# KeyBoard.net
KiCad netlist of a schematic drawn in Altium Designer
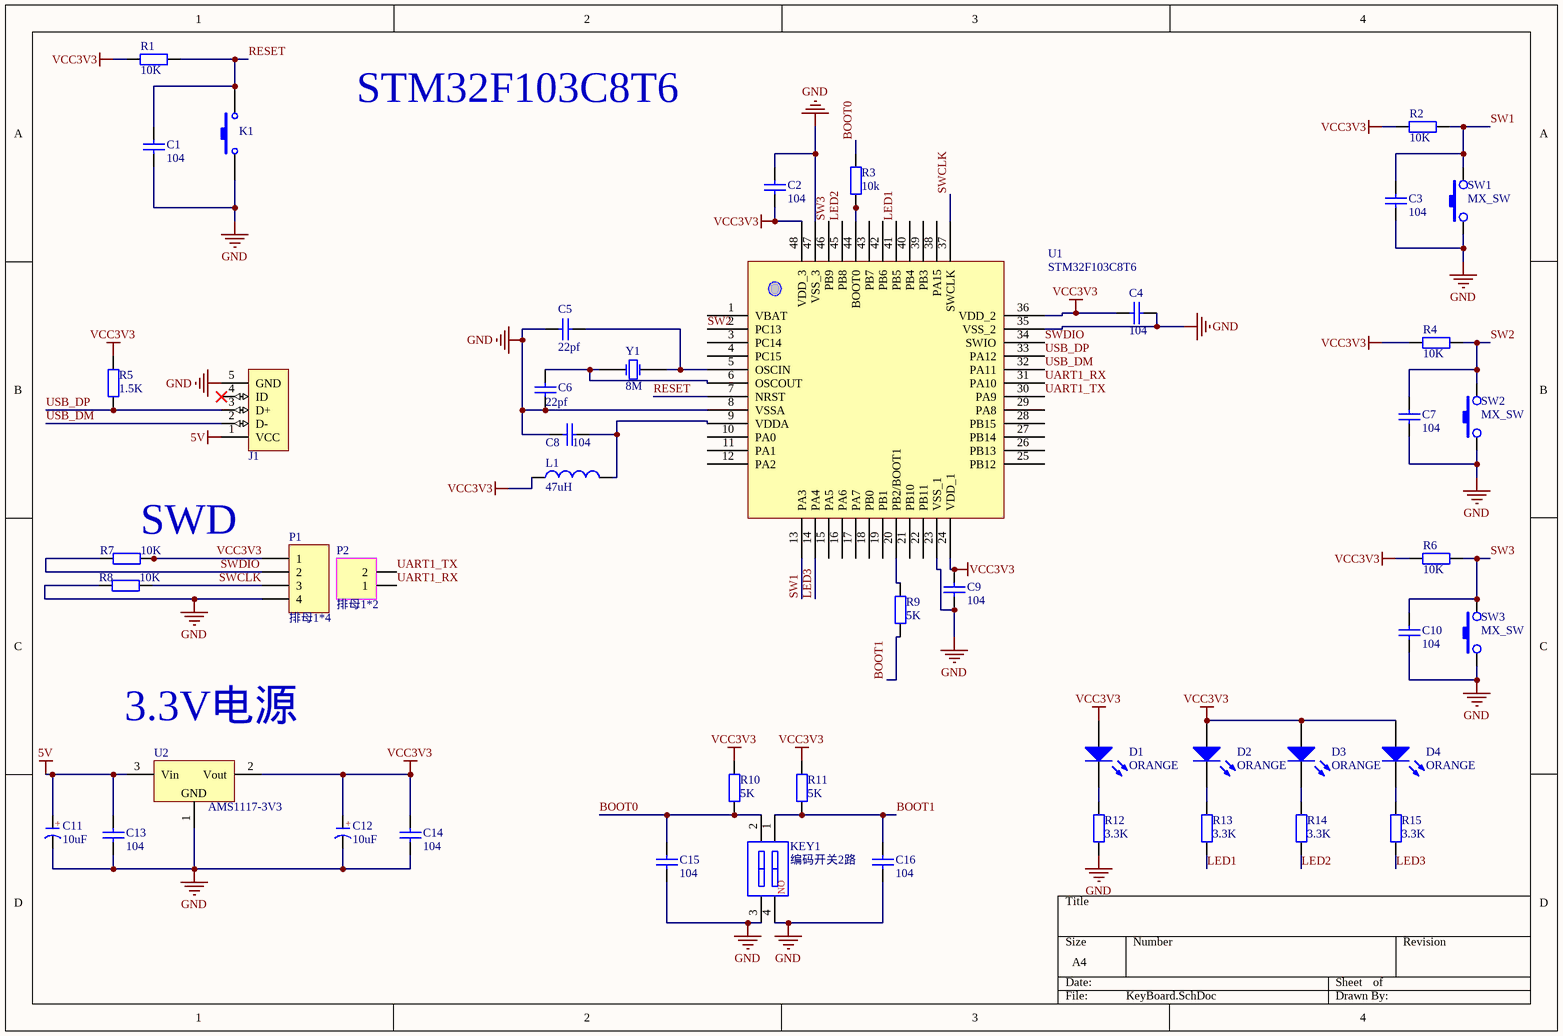
[diagram p0: KeyBoard.SchDoc]

(export (version "E")
  (design (tool "Eeschema 10.0.6"))
  (components
    (comp (ref "C1")
      (value "104")
      (footprint "C 0805")
      (description "无极性电容")
      (libsource (lib "HRT_D Schlib") (part "Cap"))
    )
    (comp (ref "C2")
      (value "104")
      (footprint "C 0805")
      (description "无极性电容")
      (libsource (lib "HRT_D Schlib") (part "Cap"))
    )
    (comp (ref "C3")
      (value "104")
      (footprint "C 0805")
      (description "无极性电容")
      (libsource (lib "HRT_D Schlib") (part "Cap"))
    )
    (comp (ref "C4")
      (value "104")
      (footprint "C 0805")
      (description "无极性电容")
      (libsource (lib "HRT_D Schlib") (part "Cap"))
    )
    (comp (ref "C5")
      (value "22pf")
      (footprint "C 0805")
      (description "无极性电容")
      (libsource (lib "HRT_D Schlib") (part "Cap"))
    )
    (comp (ref "C6")
      (value "22pf")
      (footprint "C 0805")
      (description "无极性电容")
      (libsource (lib "HRT_D Schlib") (part "Cap"))
    )
    (comp (ref "C7")
      (value "104")
      (footprint "C 0805")
      (description "无极性电容")
      (libsource (lib "HRT_D Schlib") (part "Cap"))
    )
    (comp (ref "C8")
      (value "104")
      (footprint "C 0805")
      (description "无极性电容")
      (libsource (lib "HRT_D Schlib") (part "Cap"))
    )
    (comp (ref "C9")
      (value "104")
      (footprint "C 0805")
      (description "无极性电容")
      (libsource (lib "HRT_D Schlib") (part "Cap"))
    )
    (comp (ref "C10")
      (value "104")
      (footprint "C 0805")
      (description "无极性电容")
      (libsource (lib "HRT_D Schlib") (part "Cap"))
    )
    (comp (ref "C11") (value "10uF") (footprint "CD B(3528)") (libsource (lib "电阻电容电感") (part "贴片钽电容")))
    (comp (ref "C12") (value "10uF") (footprint "CD B(3528)") (libsource (lib "电阻电容电感") (part "贴片钽电容")))
    (comp (ref "C13")
      (value "104")
      (footprint "C 0805")
      (description "无极性电容")
      (libsource (lib "HRT_D Schlib") (part "Cap"))
    )
    (comp (ref "C14")
      (value "104")
      (footprint "C 0805")
      (description "无极性电容")
      (libsource (lib "HRT_D Schlib") (part "Cap"))
    )
    (comp (ref "C15")
      (value "104")
      (footprint "C 0805")
      (description "无极性电容")
      (libsource (lib "HRT_D Schlib") (part "Cap"))
    )
    (comp (ref "C16")
      (value "104")
      (footprint "C 0805")
      (description "无极性电容")
      (libsource (lib "HRT_D Schlib") (part "Cap"))
    )
    (comp (ref "D1")
      (value "ORANGE")
      (footprint "LED_0805")
      (description "发光二极管")
      (libsource (lib "ESC_control") (part "LED"))
    )
    (comp (ref "D2")
      (value "ORANGE")
      (footprint "LED_0805")
      (description "发光二极管")
      (libsource (lib "ESC_control") (part "LED"))
    )
    (comp (ref "D3")
      (value "ORANGE")
      (footprint "LED_0805")
      (description "发光二极管")
      (libsource (lib "ESC_control") (part "LED"))
    )
    (comp (ref "D4")
      (value "ORANGE")
      (footprint "LED_0805")
      (description "发光二极管")
      (libsource (lib "ESC_control") (part "LED"))
    )
    (comp (ref "J1")
      (value "Micro USB 2.0 PORT")
      (footprint "USB_MICRO")
      (description "Micro USB 2.0 插座")
      (libsource (lib "HRT_D Schlib") (part "Micro USB 2.0 PORT"))
    )
    (comp (ref "K1")
      (value "Key")
      (footprint "KEY 3.6*2.5 SMD")
      (description "按键")
      (libsource (lib "HRT_D Schlib") (part "Key"))
    )
    (comp (ref "KEY1")
      (value "编码开关2路")
      (footprint "CSW1.27 SMD-2P")
      (libsource (lib "开关、按钮") (part "编码开关2路"))
    )
    (comp (ref "L1")
      (value "47uH")
      (footprint "L 0805")
      (description "电感")
      (libsource (lib "HRT_D Schlib") (part "Inductor"))
    )
    (comp (ref "P1") (value "排母1*4") (footprint "HDR2.54-M-LI-4P") (libsource (lib "排针排母库") (part "排母1*4")))
    (comp (ref "P2") (value "排母1*2") (footprint "HDR2.54-M-LI-2P") (libsource (lib "排针排母库") (part "排母1*2")))
    (comp (ref "R1")
      (value "10K")
      (footprint "R 0805")
      (description "电阻")
      (libsource (lib "") (part "Resistor_1"))
    )
    (comp (ref "R2")
      (value "10K")
      (footprint "R 0805")
      (description "电阻")
      (libsource (lib "") (part "Resistor_1"))
    )
    (comp (ref "R3")
      (value "10k")
      (footprint "R 0805")
      (description "电阻")
      (libsource (lib "ESC_control") (part "Resistor"))
    )
    (comp (ref "R4")
      (value "10K")
      (footprint "R 0805")
      (description "电阻")
      (libsource (lib "") (part "Resistor_1"))
    )
    (comp (ref "R5")
      (value "1.5K")
      (footprint "R 0805")
      (description "电阻")
      (libsource (lib "HRT_D Schlib") (part "Resistor"))
    )
    (comp (ref "R6")
      (value "10K")
      (footprint "R 0805")
      (description "电阻")
      (libsource (lib "") (part "Resistor_1"))
    )
    (comp (ref "R7")
      (value "10K")
      (footprint "R 0805")
      (description "电阻")
      (libsource (lib "") (part "Resistor_2"))
    )
    (comp (ref "R8")
      (value "10K")
      (footprint "R 0805")
      (description "电阻")
      (libsource (lib "") (part "Resistor_2"))
    )
    (comp (ref "R9")
      (value "5K")
      (footprint "R 0805")
      (description "电阻")
      (libsource (lib "HRT_D Schlib") (part "Resistor"))
    )
    (comp (ref "R10")
      (value "5K")
      (footprint "R 0805")
      (description "电阻")
      (libsource (lib "HRT_D Schlib") (part "Resistor"))
    )
    (comp (ref "R11")
      (value "5K")
      (footprint "R 0805")
      (description "电阻")
      (libsource (lib "HRT_D Schlib") (part "Resistor"))
    )
    (comp (ref "R12")
      (value "3.3K")
      (footprint "R 0805")
      (description "电阻")
      (libsource (lib "HRT_D Schlib") (part "Resistor"))
    )
    (comp (ref "R13")
      (value "3.3K")
      (footprint "R 0805")
      (description "电阻")
      (libsource (lib "HRT_D Schlib") (part "Resistor"))
    )
    (comp (ref "R14")
      (value "3.3K")
      (footprint "R 0805")
      (description "电阻")
      (libsource (lib "HRT_D Schlib") (part "Resistor"))
    )
    (comp (ref "R15")
      (value "3.3K")
      (footprint "R 0805")
      (description "电阻")
      (libsource (lib "HRT_D Schlib") (part "Resistor"))
    )
    (comp (ref "SW1")
      (value "MX_SW")
      (footprint "MX_SW-4")
      (description "with Fixation pins  1-Pole")
      (libsource (lib "KeyBoard") (part "MX_SW-4"))
    )
    (comp (ref "SW2")
      (value "MX_SW")
      (footprint "MX_SW-4")
      (description "with Fixation pins  1-Pole")
      (libsource (lib "KeyBoard") (part "MX_SW-4"))
    )
    (comp (ref "SW3")
      (value "MX_SW")
      (footprint "MX_SW-4")
      (description "with Fixation pins  1-Pole")
      (libsource (lib "KeyBoard") (part "MX_SW-4"))
    )
    (comp (ref "U1")
      (value "STM32F103C8T6")
      (footprint "LQFP48")
      (description "Micro controller")
      (libsource (lib "HRT_D Schlib") (part "STM32F103C8T6"))
    )
    (comp (ref "U2")
      (value "AMS1117-3V3")
      (footprint "SOT223_N")
      (description "三端稳压芯片")
      (fields (field (name "版权归属") "源创客"))
      (libsource (lib "电源类（稳压）芯片") (part "AMS1117"))
    )
    (comp (ref "Y1")
      (value "8M")
      (footprint "XTAL-5032")
      (description "晶振")
      (libsource (lib "ESC_control") (part "XTAL"))
    )
  )
  (nets
    (net (code "1") (name "/BOOT0") (class "Default")
      (node (ref "C15") (pin "2") (pinfunction "2_2") (pintype "passive"))
      (node (ref "KEY1") (pin "2") (pinfunction "2_2") (pintype "passive"))
      (node (ref "R10") (pin "1") (pinfunction "1_1") (pintype "passive"))
      (node (ref "R3") (pin "2") (pinfunction "2_2") (pintype "passive"))
    )
    (net (code "2") (name "/BOOT1") (class "Default")
      (node (ref "C16") (pin "2") (pinfunction "2_2") (pintype "passive"))
      (node (ref "KEY1") (pin "1") (pinfunction "1_1") (pintype "passive"))
      (node (ref "R11") (pin "1") (pinfunction "1_1") (pintype "passive"))
      (node (ref "R9") (pin "1") (pinfunction "1_1") (pintype "passive"))
    )
    (net (code "3") (name "/LED1") (class "Default")
      (node (ref "R13") (pin "1") (pinfunction "1_1") (pintype "passive"))
      (node (ref "U1") (pin "41") (pinfunction "PB5_41") (pintype "passive"))
    )
    (net (code "4") (name "/LED2") (class "Default")
      (node (ref "R14") (pin "1") (pinfunction "1_1") (pintype "passive"))
      (node (ref "U1") (pin "45") (pinfunction "PB8_45") (pintype "passive"))
    )
    (net (code "5") (name "/LED3") (class "Default")
      (node (ref "R15") (pin "1") (pinfunction "1_1") (pintype "passive"))
      (node (ref "U1") (pin "14") (pinfunction "PA4_14") (pintype "passive"))
    )
    (net (code "6") (name "/RESET") (class "Default")
      (node (ref "C1") (pin "2") (pinfunction "2_2") (pintype "passive"))
      (node (ref "K1") (pin "2") (pinfunction "2_2") (pintype "passive"))
      (node (ref "R1") (pin "2") (pinfunction "2_2") (pintype "passive"))
      (node (ref "U1") (pin "7") (pinfunction "NRST_7") (pintype "passive"))
    )
    (net (code "7") (name "/SW1") (class "Default")
      (node (ref "C3") (pin "2") (pinfunction "2_2") (pintype "passive"))
      (node (ref "R2") (pin "2") (pinfunction "2_2") (pintype "passive"))
      (node (ref "SW1") (pin "2") (pinfunction "2_2") (pintype "passive"))
      (node (ref "U1") (pin "13") (pinfunction "PA3_13") (pintype "passive"))
    )
    (net (code "8") (name "/SW2") (class "Default")
      (node (ref "C7") (pin "2") (pinfunction "2_2") (pintype "passive"))
      (node (ref "R4") (pin "2") (pinfunction "2_2") (pintype "passive"))
      (node (ref "SW2") (pin "2") (pinfunction "2_2") (pintype "passive"))
      (node (ref "U1") (pin "2") (pinfunction "PC13_2") (pintype "passive"))
    )
    (net (code "9") (name "/SW3") (class "Default")
      (node (ref "C10") (pin "2") (pinfunction "2_2") (pintype "passive"))
      (node (ref "R6") (pin "2") (pinfunction "2_2") (pintype "passive"))
      (node (ref "SW3") (pin "2") (pinfunction "2_2") (pintype "passive"))
      (node (ref "U1") (pin "46") (pinfunction "PB9_46") (pintype "passive"))
    )
    (net (code "10") (name "/SWCLK") (class "Default")
      (node (ref "P1") (pin "3") (pinfunction "3_3") (pintype "passive"))
      (node (ref "R8") (pin "1") (pinfunction "1_1") (pintype "passive"))
      (node (ref "U1") (pin "37") (pinfunction "SWCLK_37") (pintype "passive"))
    )
    (net (code "11") (name "/SWDIO") (class "Default")
      (node (ref "P1") (pin "2") (pinfunction "2_2") (pintype "passive"))
      (node (ref "R7") (pin "2") (pinfunction "2_2") (pintype "passive"))
      (node (ref "U1") (pin "34") (pinfunction "SWIO_34") (pintype "passive"))
    )
    (net (code "12") (name "/UART1_RX") (class "Default")
      (node (ref "P2") (pin "1") (pinfunction "1_1") (pintype "passive"))
      (node (ref "U1") (pin "31") (pinfunction "PA10_31") (pintype "passive"))
    )
    (net (code "13") (name "/UART1_TX") (class "Default")
      (node (ref "P2") (pin "2") (pinfunction "2_2") (pintype "passive"))
      (node (ref "U1") (pin "30") (pinfunction "PA9_30") (pintype "passive"))
    )
    (net (code "14") (name "/USB_DM") (class "Default")
      (node (ref "J1") (pin "2") (pinfunction "D-_2") (pintype "bidirectional"))
      (node (ref "U1") (pin "32") (pinfunction "PA11_32") (pintype "passive"))
    )
    (net (code "15") (name "/USB_DP") (class "Default")
      (node (ref "J1") (pin "3") (pinfunction "D+_3") (pintype "bidirectional"))
      (node (ref "R5") (pin "1") (pinfunction "1_1") (pintype "passive"))
      (node (ref "U1") (pin "33") (pinfunction "PA12_33") (pintype "passive"))
    )
    (net (code "16") (name "5V") (class "Default")
      (node (ref "C11") (pin "1") (pinfunction "A_1") (pintype "passive"))
      (node (ref "C13") (pin "2") (pinfunction "2_2") (pintype "passive"))
      (node (ref "J1") (pin "1") (pinfunction "VCC_1") (pintype "power_in"))
      (node (ref "U2") (pin "3") (pinfunction "Vin_3") (pintype "passive"))
    )
    (net (code "17") (name "GND") (class "Default")
      (node (ref "C1") (pin "1") (pinfunction "1_1") (pintype "passive"))
      (node (ref "C10") (pin "1") (pinfunction "1_1") (pintype "passive"))
      (node (ref "C11") (pin "2") (pinfunction "K_2") (pintype "passive"))
      (node (ref "C12") (pin "2") (pinfunction "K_2") (pintype "passive"))
      (node (ref "C13") (pin "1") (pinfunction "1_1") (pintype "passive"))
      (node (ref "C14") (pin "1") (pinfunction "1_1") (pintype "passive"))
      (node (ref "C15") (pin "1") (pinfunction "1_1") (pintype "passive"))
      (node (ref "C16") (pin "1") (pinfunction "1_1") (pintype "passive"))
      (node (ref "C2") (pin "2") (pinfunction "2_2") (pintype "passive"))
      (node (ref "C3") (pin "1") (pinfunction "1_1") (pintype "passive"))
      (node (ref "C4") (pin "1") (pinfunction "1_1") (pintype "passive"))
      (node (ref "C5") (pin "2") (pinfunction "2_2") (pintype "passive"))
      (node (ref "C6") (pin "2") (pinfunction "2_2") (pintype "passive"))
      (node (ref "C7") (pin "1") (pinfunction "1_1") (pintype "passive"))
      (node (ref "C8") (pin "2") (pinfunction "2_2") (pintype "passive"))
      (node (ref "C9") (pin "1") (pinfunction "1_1") (pintype "passive"))
      (node (ref "J1") (pin "5") (pinfunction "GND_5") (pintype "power_in"))
      (node (ref "K1") (pin "1") (pinfunction "1_1") (pintype "passive"))
      (node (ref "KEY1") (pin "3") (pinfunction "3_3") (pintype "passive"))
      (node (ref "KEY1") (pin "4") (pinfunction "4_4") (pintype "passive"))
      (node (ref "P1") (pin "4") (pinfunction "4_4") (pintype "passive"))
      (node (ref "R12") (pin "1") (pinfunction "1_1") (pintype "passive"))
      (node (ref "R8") (pin "2") (pinfunction "2_2") (pintype "passive"))
      (node (ref "SW1") (pin "1") (pinfunction "1_1") (pintype "passive"))
      (node (ref "SW2") (pin "1") (pinfunction "1_1") (pintype "passive"))
      (node (ref "SW3") (pin "1") (pinfunction "1_1") (pintype "passive"))
      (node (ref "U1") (pin "23") (pinfunction "VSS_1_23") (pintype "passive"))
      (node (ref "U1") (pin "35") (pinfunction "VSS_2_35") (pintype "passive"))
      (node (ref "U1") (pin "47") (pinfunction "VSS_3_47") (pintype "passive"))
      (node (ref "U1") (pin "8") (pinfunction "VSSA_8") (pintype "passive"))
      (node (ref "U2") (pin "1") (pinfunction "GND_1") (pintype "passive"))
    )
    (net (code "18") (name "Net-(D1-K)") (class "Default")
      (node (ref "D1") (pin "2") (pinfunction "K_2") (pintype "passive"))
      (node (ref "R12") (pin "2") (pinfunction "2_2") (pintype "passive"))
    )
    (net (code "19") (name "Net-(D2-K)") (class "Default")
      (node (ref "D2") (pin "2") (pinfunction "K_2") (pintype "passive"))
      (node (ref "R13") (pin "2") (pinfunction "2_2") (pintype "passive"))
    )
    (net (code "20") (name "Net-(D3-K)") (class "Default")
      (node (ref "D3") (pin "2") (pinfunction "K_2") (pintype "passive"))
      (node (ref "R14") (pin "2") (pinfunction "2_2") (pintype "passive"))
    )
    (net (code "21") (name "Net-(D4-K)") (class "Default")
      (node (ref "D4") (pin "2") (pinfunction "K_2") (pintype "passive"))
      (node (ref "R15") (pin "2") (pinfunction "2_2") (pintype "passive"))
    )
    (net (code "22") (name "Net-(U1-BOOT0)") (class "Default")
      (node (ref "R3") (pin "1") (pinfunction "1_1") (pintype "passive"))
      (node (ref "U1") (pin "44") (pinfunction "BOOT0_44") (pintype "passive"))
    )
    (net (code "23") (name "Net-(U1-OSCIN)") (class "Default")
      (node (ref "C5") (pin "1") (pinfunction "1_1") (pintype "passive"))
      (node (ref "U1") (pin "5") (pinfunction "OSCIN_5") (pintype "passive"))
      (node (ref "Y1") (pin "2") (pinfunction "OSC2_2") (pintype "passive"))
    )
    (net (code "24") (name "Net-(U1-OSCOUT)") (class "Default")
      (node (ref "C6") (pin "1") (pinfunction "1_1") (pintype "passive"))
      (node (ref "U1") (pin "6") (pinfunction "OSCOUT_6") (pintype "passive"))
      (node (ref "Y1") (pin "1") (pinfunction "OSC1_1") (pintype "passive"))
    )
    (net (code "25") (name "Net-(U1-PB2{slash}BOOT1)") (class "Default")
      (node (ref "R9") (pin "2") (pinfunction "2_2") (pintype "passive"))
      (node (ref "U1") (pin "20") (pinfunction "PB2/BOOT1_20") (pintype "passive"))
    )
    (net (code "26") (name "Net-(U1-VDDA)") (class "Default")
      (node (ref "C8") (pin "1") (pinfunction "1_1") (pintype "passive"))
      (node (ref "L1") (pin "2") (pinfunction "2_2") (pintype "passive"))
      (node (ref "U1") (pin "9") (pinfunction "VDDA_9") (pintype "passive"))
    )
    (net (code "27") (name "VCC3V3") (class "Default")
      (node (ref "C12") (pin "1") (pinfunction "A_1") (pintype "passive"))
      (node (ref "C14") (pin "2") (pinfunction "2_2") (pintype "passive"))
      (node (ref "C2") (pin "1") (pinfunction "1_1") (pintype "passive"))
      (node (ref "C4") (pin "2") (pinfunction "2_2") (pintype "passive"))
      (node (ref "C9") (pin "2") (pinfunction "2_2") (pintype "passive"))
      (node (ref "D1") (pin "1") (pinfunction "A_1") (pintype "passive"))
      (node (ref "D2") (pin "1") (pinfunction "A_1") (pintype "passive"))
      (node (ref "D3") (pin "1") (pinfunction "A_1") (pintype "passive"))
      (node (ref "D4") (pin "1") (pinfunction "A_1") (pintype "passive"))
      (node (ref "L1") (pin "1") (pinfunction "1_1") (pintype "passive"))
      (node (ref "P1") (pin "1") (pinfunction "1_1") (pintype "passive"))
      (node (ref "R1") (pin "1") (pinfunction "1_1") (pintype "passive"))
      (node (ref "R10") (pin "2") (pinfunction "2_2") (pintype "passive"))
      (node (ref "R11") (pin "2") (pinfunction "2_2") (pintype "passive"))
      (node (ref "R2") (pin "1") (pinfunction "1_1") (pintype "passive"))
      (node (ref "R4") (pin "1") (pinfunction "1_1") (pintype "passive"))
      (node (ref "R5") (pin "2") (pinfunction "2_2") (pintype "passive"))
      (node (ref "R6") (pin "1") (pinfunction "1_1") (pintype "passive"))
      (node (ref "R7") (pin "1") (pinfunction "1_1") (pintype "passive"))
      (node (ref "U1") (pin "24") (pinfunction "VDD_1_24") (pintype "passive"))
      (node (ref "U1") (pin "36") (pinfunction "VDD_2_36") (pintype "passive"))
      (node (ref "U1") (pin "48") (pinfunction "VDD_3_48") (pintype "passive"))
      (node (ref "U2") (pin "2") (pinfunction "Vout_2") (pintype "passive"))
    )
    (net (code "28") (name "unconnected-(J1-ID-Pad4)") (class "Default")
      (node (ref "J1") (pin "4") (pinfunction "ID_4") (pintype "bidirectional+no_connect"))
    )
    (net (code "29") (name "unconnected-(U1-PA0-Pad10)") (class "Default")
      (node (ref "U1") (pin "10") (pinfunction "PA0_10") (pintype "passive"))
    )
    (net (code "30") (name "unconnected-(U1-PA1-Pad11)") (class "Default")
      (node (ref "U1") (pin "11") (pinfunction "PA1_11") (pintype "passive"))
    )
    (net (code "31") (name "unconnected-(U1-PA2-Pad12)") (class "Default")
      (node (ref "U1") (pin "12") (pinfunction "PA2_12") (pintype "passive"))
    )
    (net (code "32") (name "unconnected-(U1-PA5-Pad15)") (class "Default")
      (node (ref "U1") (pin "15") (pinfunction "PA5_15") (pintype "passive"))
    )
    (net (code "33") (name "unconnected-(U1-PA6-Pad16)") (class "Default")
      (node (ref "U1") (pin "16") (pinfunction "PA6_16") (pintype "passive"))
    )
    (net (code "34") (name "unconnected-(U1-PA7-Pad17)") (class "Default")
      (node (ref "U1") (pin "17") (pinfunction "PA7_17") (pintype "passive"))
    )
    (net (code "35") (name "unconnected-(U1-PA8-Pad29)") (class "Default")
      (node (ref "U1") (pin "29") (pinfunction "PA8_29") (pintype "passive"))
    )
    (net (code "36") (name "unconnected-(U1-PA15-Pad38)") (class "Default")
      (node (ref "U1") (pin "38") (pinfunction "PA15_38") (pintype "passive"))
    )
    (net (code "37") (name "unconnected-(U1-PB0-Pad18)") (class "Default")
      (node (ref "U1") (pin "18") (pinfunction "PB0_18") (pintype "passive"))
    )
    (net (code "38") (name "unconnected-(U1-PB1-Pad19)") (class "Default")
      (node (ref "U1") (pin "19") (pinfunction "PB1_19") (pintype "passive"))
    )
    (net (code "39") (name "unconnected-(U1-PB3-Pad39)") (class "Default")
      (node (ref "U1") (pin "39") (pinfunction "PB3_39") (pintype "passive"))
    )
    (net (code "40") (name "unconnected-(U1-PB4-Pad40)") (class "Default")
      (node (ref "U1") (pin "40") (pinfunction "PB4_40") (pintype "passive"))
    )
    (net (code "41") (name "unconnected-(U1-PB6-Pad42)") (class "Default")
      (node (ref "U1") (pin "42") (pinfunction "PB6_42") (pintype "passive"))
    )
    (net (code "42") (name "unconnected-(U1-PB7-Pad43)") (class "Default")
      (node (ref "U1") (pin "43") (pinfunction "PB7_43") (pintype "passive"))
    )
    (net (code "43") (name "unconnected-(U1-PB10-Pad21)") (class "Default")
      (node (ref "U1") (pin "21") (pinfunction "PB10_21") (pintype "passive"))
    )
    (net (code "44") (name "unconnected-(U1-PB11-Pad22)") (class "Default")
      (node (ref "U1") (pin "22") (pinfunction "PB11_22") (pintype "passive"))
    )
    (net (code "45") (name "unconnected-(U1-PB12-Pad25)") (class "Default")
      (node (ref "U1") (pin "25") (pinfunction "PB12_25") (pintype "passive"))
    )
    (net (code "46") (name "unconnected-(U1-PB13-Pad26)") (class "Default")
      (node (ref "U1") (pin "26") (pinfunction "PB13_26") (pintype "passive"))
    )
    (net (code "47") (name "unconnected-(U1-PB14-Pad27)") (class "Default")
      (node (ref "U1") (pin "27") (pinfunction "PB14_27") (pintype "passive"))
    )
    (net (code "48") (name "unconnected-(U1-PB15-Pad28)") (class "Default")
      (node (ref "U1") (pin "28") (pinfunction "PB15_28") (pintype "passive"))
    )
    (net (code "49") (name "unconnected-(U1-PC14-Pad3)") (class "Default")
      (node (ref "U1") (pin "3") (pinfunction "PC14_3") (pintype "passive"))
    )
    (net (code "50") (name "unconnected-(U1-PC15-Pad4)") (class "Default")
      (node (ref "U1") (pin "4") (pinfunction "PC15_4") (pintype "passive"))
    )
    (net (code "51") (name "unconnected-(U1-VBAT-Pad1)") (class "Default")
      (node (ref "U1") (pin "1") (pinfunction "VBAT_1") (pintype "passive"))
    )
  )
)
